# AB_shield.net
KiCad netlist of a schematic drawn in EAGLE
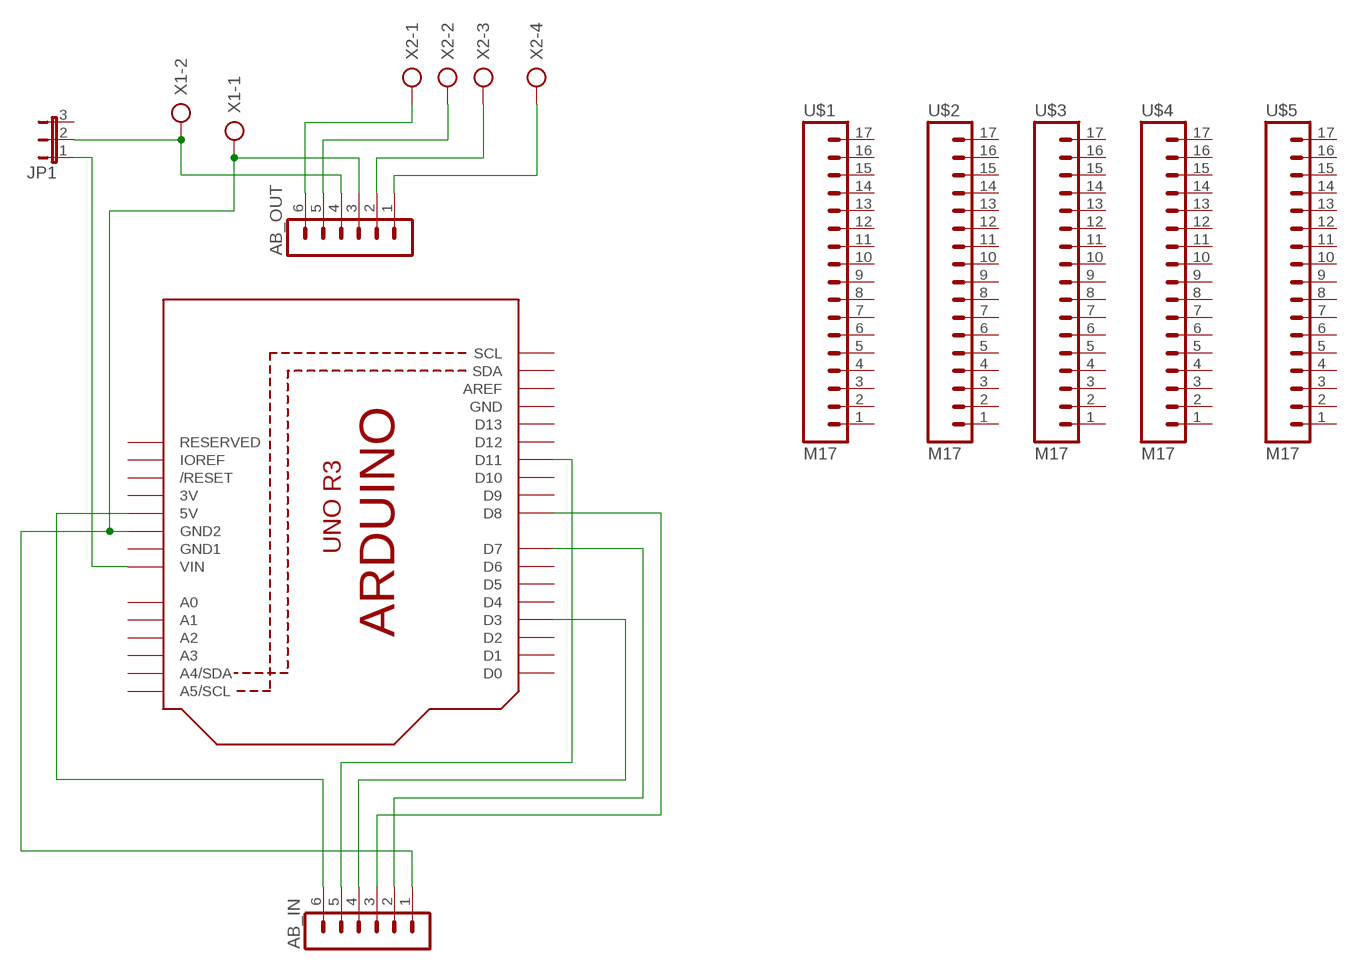
[diagram p0: schematic, sheet 1]

(export (version "E")
  (design (tool "Eeschema 10.0.6"))
  (components
    (comp (ref "AB_IN")
      (value "MA06-1")
      (footprint "eagle-import:MA06-1")
      (libsource (lib "eagle-import") (part "MA06-1"))
    )
    (comp (ref "AB_OUT")
      (value "MA06-1")
      (footprint "eagle-import:MA06-1")
      (libsource (lib "eagle-import") (part "MA06-1"))
    )
    (comp (ref "JP1")
      (value "JP2E")
      (footprint "eagle-import:JP2")
      (libsource (lib "eagle-import") (part "JP2E"))
    )
    (comp (ref "U$1")
      (value "M17")
      (footprint "eagle-import:1X17_PROTO")
      (libsource (lib "eagle-import") (part "M17"))
    )
    (comp (ref "U$2")
      (value "M17")
      (footprint "eagle-import:1X17_PROTO")
      (libsource (lib "eagle-import") (part "M17"))
    )
    (comp (ref "U$3")
      (value "M17")
      (footprint "eagle-import:1X17_PROTO")
      (libsource (lib "eagle-import") (part "M17"))
    )
    (comp (ref "U$4")
      (value "M17")
      (footprint "eagle-import:1X17_PROTO")
      (libsource (lib "eagle-import") (part "M17"))
    )
    (comp (ref "U$5")
      (value "M17")
      (footprint "eagle-import:1X17_PROTO")
      (libsource (lib "eagle-import") (part "M17"))
    )
    (comp (ref "U1")
      (value "ARDUINOR3-DIMENSION")
      (footprint "eagle-import:ARDUINOR3")
      (libsource (lib "eagle-import") (part "ARDUINOR3-DIMENSION"))
    )
    (comp (ref "X1")
      (value "AK500/2-H")
      (footprint "eagle-import:AK500_2-H")
      (libsource (lib "eagle-import") (part "AK500/2-H"))
    )
    (comp (ref "X2")
      (value "AK500/4")
      (footprint "eagle-import:AK500_4")
      (libsource (lib "eagle-import") (part "AK500/4"))
    )
  )
  (nets
    (net (code "1") (name "/3V") (class "Default")
      (node (ref "U1") (pin "3V") (pinfunction "3V_3V") (pintype "power_in"))
    )
    (net (code "2") (name "/GND") (class "Default")
      (node (ref "U1") (pin "GND") (pinfunction "GND_GND") (pintype "power_in"))
    )
    (net (code "3") (name "/GND1") (class "Default")
      (node (ref "U1") (pin "GND1") (pinfunction "GND1_GND1") (pintype "power_in"))
    )
    (net (code "4") (name "Net-(AB_IN-Pad2)") (class "Default")
      (node (ref "AB_IN") (pin "2") (pinfunction "2_2") (pintype "passive"))
      (node (ref "U1") (pin "D7") (pinfunction "D7_D7") (pintype "bidirectional"))
    )
    (net (code "5") (name "Net-(AB_IN-Pad3)") (class "Default")
      (node (ref "AB_IN") (pin "3") (pinfunction "3_3") (pintype "passive"))
      (node (ref "U1") (pin "D8") (pinfunction "D8_D8") (pintype "bidirectional"))
    )
    (net (code "6") (name "Net-(AB_IN-Pad4)") (class "Default")
      (node (ref "AB_IN") (pin "4") (pinfunction "4_4") (pintype "passive"))
      (node (ref "U1") (pin "D3") (pinfunction "D3_D3") (pintype "bidirectional"))
    )
    (net (code "7") (name "Net-(AB_IN-Pad5)") (class "Default")
      (node (ref "AB_IN") (pin "5") (pinfunction "5_5") (pintype "passive"))
      (node (ref "U1") (pin "D11") (pinfunction "D11_D11") (pintype "bidirectional"))
    )
    (net (code "8") (name "Net-(AB_IN-Pad6)") (class "Default")
      (node (ref "AB_IN") (pin "6") (pinfunction "6_6") (pintype "passive"))
      (node (ref "U1") (pin "5V") (pinfunction "5V_5V") (pintype "power_in"))
    )
    (net (code "9") (name "Net-(JP1-Pad1)") (class "Default")
      (node (ref "JP1") (pin "1") (pinfunction "1_1") (pintype "passive"))
      (node (ref "U1") (pin "VIN") (pinfunction "VIN_VIN") (pintype "power_in"))
    )
    (net (code "10") (name "Net-(X1A-KL)") (class "Default")
      (node (ref "AB_IN") (pin "1") (pinfunction "1_1") (pintype "passive"))
      (node (ref "AB_OUT") (pin "3") (pinfunction "3_3") (pintype "passive"))
      (node (ref "U1") (pin "GND2") (pinfunction "GND2_GND2") (pintype "power_in"))
      (node (ref "X1") (pin "1") (pinfunction "KL_1") (pintype "passive"))
    )
    (net (code "11") (name "Net-(X1B-KL)") (class "Default")
      (node (ref "AB_OUT") (pin "4") (pinfunction "4_4") (pintype "passive"))
      (node (ref "JP1") (pin "2") (pinfunction "2_2") (pintype "passive"))
      (node (ref "X1") (pin "2") (pinfunction "KL_2") (pintype "passive"))
    )
    (net (code "12") (name "Net-(X2A-KL)") (class "Default")
      (node (ref "AB_OUT") (pin "6") (pinfunction "6_6") (pintype "passive"))
      (node (ref "X2") (pin "1") (pinfunction "KL_1") (pintype "passive"))
    )
    (net (code "13") (name "Net-(X2B-KL)") (class "Default")
      (node (ref "AB_OUT") (pin "5") (pinfunction "5_5") (pintype "passive"))
      (node (ref "X2") (pin "2") (pinfunction "KL_2") (pintype "passive"))
    )
    (net (code "14") (name "Net-(X2C-KL)") (class "Default")
      (node (ref "AB_OUT") (pin "2") (pinfunction "2_2") (pintype "passive"))
      (node (ref "X2") (pin "3") (pinfunction "KL_3") (pintype "passive"))
    )
    (net (code "15") (name "Net-(X2D-KL)") (class "Default")
      (node (ref "AB_OUT") (pin "1") (pinfunction "1_1") (pintype "passive"))
      (node (ref "X2") (pin "4") (pinfunction "KL_4") (pintype "passive"))
    )
    (net (code "16") (name "unconnected-(JP1-Pad3)") (class "Default")
      (node (ref "JP1") (pin "3") (pinfunction "3_3") (pintype "passive"))
    )
    (net (code "17") (name "unconnected-(U$1-Pad1)") (class "Default")
      (node (ref "U$1") (pin "1") (pinfunction "1_1") (pintype "passive"))
    )
    (net (code "18") (name "unconnected-(U$1-Pad2)") (class "Default")
      (node (ref "U$1") (pin "2") (pinfunction "2_2") (pintype "passive"))
    )
    (net (code "19") (name "unconnected-(U$1-Pad3)") (class "Default")
      (node (ref "U$1") (pin "3") (pinfunction "3_3") (pintype "passive"))
    )
    (net (code "20") (name "unconnected-(U$1-Pad4)") (class "Default")
      (node (ref "U$1") (pin "4") (pinfunction "4_4") (pintype "passive"))
    )
    (net (code "21") (name "unconnected-(U$1-Pad5)") (class "Default")
      (node (ref "U$1") (pin "5") (pinfunction "5_5") (pintype "passive"))
    )
    (net (code "22") (name "unconnected-(U$1-Pad6)") (class "Default")
      (node (ref "U$1") (pin "6") (pinfunction "6_6") (pintype "passive"))
    )
    (net (code "23") (name "unconnected-(U$1-Pad7)") (class "Default")
      (node (ref "U$1") (pin "7") (pinfunction "7_7") (pintype "passive"))
    )
    (net (code "24") (name "unconnected-(U$1-Pad8)") (class "Default")
      (node (ref "U$1") (pin "8") (pinfunction "8_8") (pintype "passive"))
    )
    (net (code "25") (name "unconnected-(U$1-Pad9)") (class "Default")
      (node (ref "U$1") (pin "9") (pinfunction "9_9") (pintype "passive"))
    )
    (net (code "26") (name "unconnected-(U$1-Pad10)") (class "Default")
      (node (ref "U$1") (pin "10") (pinfunction "10_10") (pintype "passive"))
    )
    (net (code "27") (name "unconnected-(U$1-Pad11)") (class "Default")
      (node (ref "U$1") (pin "11") (pinfunction "11_11") (pintype "passive"))
    )
    (net (code "28") (name "unconnected-(U$1-Pad12)") (class "Default")
      (node (ref "U$1") (pin "12") (pinfunction "12_12") (pintype "passive"))
    )
    (net (code "29") (name "unconnected-(U$1-Pad13)") (class "Default")
      (node (ref "U$1") (pin "13") (pinfunction "13_13") (pintype "passive"))
    )
    (net (code "30") (name "unconnected-(U$1-Pad14)") (class "Default")
      (node (ref "U$1") (pin "14") (pinfunction "14_14") (pintype "passive"))
    )
    (net (code "31") (name "unconnected-(U$1-Pad15)") (class "Default")
      (node (ref "U$1") (pin "15") (pinfunction "15_15") (pintype "passive"))
    )
    (net (code "32") (name "unconnected-(U$1-Pad16)") (class "Default")
      (node (ref "U$1") (pin "16") (pinfunction "16_16") (pintype "passive"))
    )
    (net (code "33") (name "unconnected-(U$1-Pad17)") (class "Default")
      (node (ref "U$1") (pin "17") (pinfunction "17_17") (pintype "passive"))
    )
    (net (code "34") (name "unconnected-(U$2-Pad1)") (class "Default")
      (node (ref "U$2") (pin "1") (pinfunction "1_1") (pintype "passive"))
    )
    (net (code "35") (name "unconnected-(U$2-Pad2)") (class "Default")
      (node (ref "U$2") (pin "2") (pinfunction "2_2") (pintype "passive"))
    )
    (net (code "36") (name "unconnected-(U$2-Pad3)") (class "Default")
      (node (ref "U$2") (pin "3") (pinfunction "3_3") (pintype "passive"))
    )
    (net (code "37") (name "unconnected-(U$2-Pad4)") (class "Default")
      (node (ref "U$2") (pin "4") (pinfunction "4_4") (pintype "passive"))
    )
    (net (code "38") (name "unconnected-(U$2-Pad5)") (class "Default")
      (node (ref "U$2") (pin "5") (pinfunction "5_5") (pintype "passive"))
    )
    (net (code "39") (name "unconnected-(U$2-Pad6)") (class "Default")
      (node (ref "U$2") (pin "6") (pinfunction "6_6") (pintype "passive"))
    )
    (net (code "40") (name "unconnected-(U$2-Pad7)") (class "Default")
      (node (ref "U$2") (pin "7") (pinfunction "7_7") (pintype "passive"))
    )
    (net (code "41") (name "unconnected-(U$2-Pad8)") (class "Default")
      (node (ref "U$2") (pin "8") (pinfunction "8_8") (pintype "passive"))
    )
    (net (code "42") (name "unconnected-(U$2-Pad9)") (class "Default")
      (node (ref "U$2") (pin "9") (pinfunction "9_9") (pintype "passive"))
    )
    (net (code "43") (name "unconnected-(U$2-Pad10)") (class "Default")
      (node (ref "U$2") (pin "10") (pinfunction "10_10") (pintype "passive"))
    )
    (net (code "44") (name "unconnected-(U$2-Pad11)") (class "Default")
      (node (ref "U$2") (pin "11") (pinfunction "11_11") (pintype "passive"))
    )
    (net (code "45") (name "unconnected-(U$2-Pad12)") (class "Default")
      (node (ref "U$2") (pin "12") (pinfunction "12_12") (pintype "passive"))
    )
    (net (code "46") (name "unconnected-(U$2-Pad13)") (class "Default")
      (node (ref "U$2") (pin "13") (pinfunction "13_13") (pintype "passive"))
    )
    (net (code "47") (name "unconnected-(U$2-Pad14)") (class "Default")
      (node (ref "U$2") (pin "14") (pinfunction "14_14") (pintype "passive"))
    )
    (net (code "48") (name "unconnected-(U$2-Pad15)") (class "Default")
      (node (ref "U$2") (pin "15") (pinfunction "15_15") (pintype "passive"))
    )
    (net (code "49") (name "unconnected-(U$2-Pad16)") (class "Default")
      (node (ref "U$2") (pin "16") (pinfunction "16_16") (pintype "passive"))
    )
    (net (code "50") (name "unconnected-(U$2-Pad17)") (class "Default")
      (node (ref "U$2") (pin "17") (pinfunction "17_17") (pintype "passive"))
    )
    (net (code "51") (name "unconnected-(U$3-Pad1)") (class "Default")
      (node (ref "U$3") (pin "1") (pinfunction "1_1") (pintype "passive"))
    )
    (net (code "52") (name "unconnected-(U$3-Pad2)") (class "Default")
      (node (ref "U$3") (pin "2") (pinfunction "2_2") (pintype "passive"))
    )
    (net (code "53") (name "unconnected-(U$3-Pad3)") (class "Default")
      (node (ref "U$3") (pin "3") (pinfunction "3_3") (pintype "passive"))
    )
    (net (code "54") (name "unconnected-(U$3-Pad4)") (class "Default")
      (node (ref "U$3") (pin "4") (pinfunction "4_4") (pintype "passive"))
    )
    (net (code "55") (name "unconnected-(U$3-Pad5)") (class "Default")
      (node (ref "U$3") (pin "5") (pinfunction "5_5") (pintype "passive"))
    )
    (net (code "56") (name "unconnected-(U$3-Pad6)") (class "Default")
      (node (ref "U$3") (pin "6") (pinfunction "6_6") (pintype "passive"))
    )
    (net (code "57") (name "unconnected-(U$3-Pad7)") (class "Default")
      (node (ref "U$3") (pin "7") (pinfunction "7_7") (pintype "passive"))
    )
    (net (code "58") (name "unconnected-(U$3-Pad8)") (class "Default")
      (node (ref "U$3") (pin "8") (pinfunction "8_8") (pintype "passive"))
    )
    (net (code "59") (name "unconnected-(U$3-Pad9)") (class "Default")
      (node (ref "U$3") (pin "9") (pinfunction "9_9") (pintype "passive"))
    )
    (net (code "60") (name "unconnected-(U$3-Pad10)") (class "Default")
      (node (ref "U$3") (pin "10") (pinfunction "10_10") (pintype "passive"))
    )
    (net (code "61") (name "unconnected-(U$3-Pad11)") (class "Default")
      (node (ref "U$3") (pin "11") (pinfunction "11_11") (pintype "passive"))
    )
    (net (code "62") (name "unconnected-(U$3-Pad12)") (class "Default")
      (node (ref "U$3") (pin "12") (pinfunction "12_12") (pintype "passive"))
    )
    (net (code "63") (name "unconnected-(U$3-Pad13)") (class "Default")
      (node (ref "U$3") (pin "13") (pinfunction "13_13") (pintype "passive"))
    )
    (net (code "64") (name "unconnected-(U$3-Pad14)") (class "Default")
      (node (ref "U$3") (pin "14") (pinfunction "14_14") (pintype "passive"))
    )
    (net (code "65") (name "unconnected-(U$3-Pad15)") (class "Default")
      (node (ref "U$3") (pin "15") (pinfunction "15_15") (pintype "passive"))
    )
    (net (code "66") (name "unconnected-(U$3-Pad16)") (class "Default")
      (node (ref "U$3") (pin "16") (pinfunction "16_16") (pintype "passive"))
    )
    (net (code "67") (name "unconnected-(U$3-Pad17)") (class "Default")
      (node (ref "U$3") (pin "17") (pinfunction "17_17") (pintype "passive"))
    )
    (net (code "68") (name "unconnected-(U$4-Pad1)") (class "Default")
      (node (ref "U$4") (pin "1") (pinfunction "1_1") (pintype "passive"))
    )
    (net (code "69") (name "unconnected-(U$4-Pad2)") (class "Default")
      (node (ref "U$4") (pin "2") (pinfunction "2_2") (pintype "passive"))
    )
    (net (code "70") (name "unconnected-(U$4-Pad3)") (class "Default")
      (node (ref "U$4") (pin "3") (pinfunction "3_3") (pintype "passive"))
    )
    (net (code "71") (name "unconnected-(U$4-Pad4)") (class "Default")
      (node (ref "U$4") (pin "4") (pinfunction "4_4") (pintype "passive"))
    )
    (net (code "72") (name "unconnected-(U$4-Pad5)") (class "Default")
      (node (ref "U$4") (pin "5") (pinfunction "5_5") (pintype "passive"))
    )
    (net (code "73") (name "unconnected-(U$4-Pad6)") (class "Default")
      (node (ref "U$4") (pin "6") (pinfunction "6_6") (pintype "passive"))
    )
    (net (code "74") (name "unconnected-(U$4-Pad7)") (class "Default")
      (node (ref "U$4") (pin "7") (pinfunction "7_7") (pintype "passive"))
    )
    (net (code "75") (name "unconnected-(U$4-Pad8)") (class "Default")
      (node (ref "U$4") (pin "8") (pinfunction "8_8") (pintype "passive"))
    )
    (net (code "76") (name "unconnected-(U$4-Pad9)") (class "Default")
      (node (ref "U$4") (pin "9") (pinfunction "9_9") (pintype "passive"))
    )
    (net (code "77") (name "unconnected-(U$4-Pad10)") (class "Default")
      (node (ref "U$4") (pin "10") (pinfunction "10_10") (pintype "passive"))
    )
    (net (code "78") (name "unconnected-(U$4-Pad11)") (class "Default")
      (node (ref "U$4") (pin "11") (pinfunction "11_11") (pintype "passive"))
    )
    (net (code "79") (name "unconnected-(U$4-Pad12)") (class "Default")
      (node (ref "U$4") (pin "12") (pinfunction "12_12") (pintype "passive"))
    )
    (net (code "80") (name "unconnected-(U$4-Pad13)") (class "Default")
      (node (ref "U$4") (pin "13") (pinfunction "13_13") (pintype "passive"))
    )
    (net (code "81") (name "unconnected-(U$4-Pad14)") (class "Default")
      (node (ref "U$4") (pin "14") (pinfunction "14_14") (pintype "passive"))
    )
    (net (code "82") (name "unconnected-(U$4-Pad15)") (class "Default")
      (node (ref "U$4") (pin "15") (pinfunction "15_15") (pintype "passive"))
    )
    (net (code "83") (name "unconnected-(U$4-Pad16)") (class "Default")
      (node (ref "U$4") (pin "16") (pinfunction "16_16") (pintype "passive"))
    )
    (net (code "84") (name "unconnected-(U$4-Pad17)") (class "Default")
      (node (ref "U$4") (pin "17") (pinfunction "17_17") (pintype "passive"))
    )
    (net (code "85") (name "unconnected-(U$5-Pad1)") (class "Default")
      (node (ref "U$5") (pin "1") (pinfunction "1_1") (pintype "passive"))
    )
    (net (code "86") (name "unconnected-(U$5-Pad2)") (class "Default")
      (node (ref "U$5") (pin "2") (pinfunction "2_2") (pintype "passive"))
    )
    (net (code "87") (name "unconnected-(U$5-Pad3)") (class "Default")
      (node (ref "U$5") (pin "3") (pinfunction "3_3") (pintype "passive"))
    )
    (net (code "88") (name "unconnected-(U$5-Pad4)") (class "Default")
      (node (ref "U$5") (pin "4") (pinfunction "4_4") (pintype "passive"))
    )
    (net (code "89") (name "unconnected-(U$5-Pad5)") (class "Default")
      (node (ref "U$5") (pin "5") (pinfunction "5_5") (pintype "passive"))
    )
    (net (code "90") (name "unconnected-(U$5-Pad6)") (class "Default")
      (node (ref "U$5") (pin "6") (pinfunction "6_6") (pintype "passive"))
    )
    (net (code "91") (name "unconnected-(U$5-Pad7)") (class "Default")
      (node (ref "U$5") (pin "7") (pinfunction "7_7") (pintype "passive"))
    )
    (net (code "92") (name "unconnected-(U$5-Pad8)") (class "Default")
      (node (ref "U$5") (pin "8") (pinfunction "8_8") (pintype "passive"))
    )
    (net (code "93") (name "unconnected-(U$5-Pad9)") (class "Default")
      (node (ref "U$5") (pin "9") (pinfunction "9_9") (pintype "passive"))
    )
    (net (code "94") (name "unconnected-(U$5-Pad10)") (class "Default")
      (node (ref "U$5") (pin "10") (pinfunction "10_10") (pintype "passive"))
    )
    (net (code "95") (name "unconnected-(U$5-Pad11)") (class "Default")
      (node (ref "U$5") (pin "11") (pinfunction "11_11") (pintype "passive"))
    )
    (net (code "96") (name "unconnected-(U$5-Pad12)") (class "Default")
      (node (ref "U$5") (pin "12") (pinfunction "12_12") (pintype "passive"))
    )
    (net (code "97") (name "unconnected-(U$5-Pad13)") (class "Default")
      (node (ref "U$5") (pin "13") (pinfunction "13_13") (pintype "passive"))
    )
    (net (code "98") (name "unconnected-(U$5-Pad14)") (class "Default")
      (node (ref "U$5") (pin "14") (pinfunction "14_14") (pintype "passive"))
    )
    (net (code "99") (name "unconnected-(U$5-Pad15)") (class "Default")
      (node (ref "U$5") (pin "15") (pinfunction "15_15") (pintype "passive"))
    )
    (net (code "100") (name "unconnected-(U$5-Pad16)") (class "Default")
      (node (ref "U$5") (pin "16") (pinfunction "16_16") (pintype "passive"))
    )
    (net (code "101") (name "unconnected-(U$5-Pad17)") (class "Default")
      (node (ref "U$5") (pin "17") (pinfunction "17_17") (pintype "passive"))
    )
    (net (code "102") (name "unconnected-(U1-A4{slash}SDA-PadA4)") (class "Default")
      (node (ref "U1") (pin "A4") (pinfunction "A4/SDA_A4") (pintype "bidirectional"))
    )
    (net (code "103") (name "unconnected-(U1-A5{slash}SCL-PadA5)") (class "Default")
      (node (ref "U1") (pin "A5") (pinfunction "A5/SCL_A5") (pintype "bidirectional"))
    )
    (net (code "104") (name "unconnected-(U1-PadA0)") (class "Default")
      (node (ref "U1") (pin "A0") (pinfunction "A0_A0") (pintype "bidirectional"))
    )
    (net (code "105") (name "unconnected-(U1-PadA1)") (class "Default")
      (node (ref "U1") (pin "A1") (pinfunction "A1_A1") (pintype "bidirectional"))
    )
    (net (code "106") (name "unconnected-(U1-PadA2)") (class "Default")
      (node (ref "U1") (pin "A2") (pinfunction "A2_A2") (pintype "bidirectional"))
    )
    (net (code "107") (name "unconnected-(U1-PadA3)") (class "Default")
      (node (ref "U1") (pin "A3") (pinfunction "A3_A3") (pintype "bidirectional"))
    )
    (net (code "108") (name "unconnected-(U1-PadAREF)") (class "Default")
      (node (ref "U1") (pin "AREF") (pinfunction "AREF_AREF") (pintype "bidirectional"))
    )
    (net (code "109") (name "unconnected-(U1-PadD0)") (class "Default")
      (node (ref "U1") (pin "D0") (pinfunction "D0_D0") (pintype "bidirectional"))
    )
    (net (code "110") (name "unconnected-(U1-PadD1)") (class "Default")
      (node (ref "U1") (pin "D1") (pinfunction "D1_D1") (pintype "bidirectional"))
    )
    (net (code "111") (name "unconnected-(U1-PadD2)") (class "Default")
      (node (ref "U1") (pin "D2") (pinfunction "D2_D2") (pintype "bidirectional"))
    )
    (net (code "112") (name "unconnected-(U1-PadD4)") (class "Default")
      (node (ref "U1") (pin "D4") (pinfunction "D4_D4") (pintype "bidirectional"))
    )
    (net (code "113") (name "unconnected-(U1-PadD5)") (class "Default")
      (node (ref "U1") (pin "D5") (pinfunction "D5_D5") (pintype "bidirectional"))
    )
    (net (code "114") (name "unconnected-(U1-PadD6)") (class "Default")
      (node (ref "U1") (pin "D6") (pinfunction "D6_D6") (pintype "bidirectional"))
    )
    (net (code "115") (name "unconnected-(U1-PadD9)") (class "Default")
      (node (ref "U1") (pin "D9") (pinfunction "D9_D9") (pintype "bidirectional"))
    )
    (net (code "116") (name "unconnected-(U1-PadD10)") (class "Default")
      (node (ref "U1") (pin "D10") (pinfunction "D10_D10") (pintype "bidirectional"))
    )
    (net (code "117") (name "unconnected-(U1-PadD12)") (class "Default")
      (node (ref "U1") (pin "D12") (pinfunction "D12_D12") (pintype "bidirectional"))
    )
    (net (code "118") (name "unconnected-(U1-PadD13)") (class "Default")
      (node (ref "U1") (pin "D13") (pinfunction "D13_D13") (pintype "bidirectional"))
    )
    (net (code "119") (name "unconnected-(U1-PadIOREF)") (class "Default")
      (node (ref "U1") (pin "IOREF") (pinfunction "IOREF_IOREF") (pintype "output"))
    )
    (net (code "120") (name "unconnected-(U1-PadRESERVED)") (class "Default")
      (node (ref "U1") (pin "RESERVED") (pinfunction "RESERVED_RESERVED") (pintype "no_connect"))
    )
    (net (code "121") (name "unconnected-(U1-PadSCL)") (class "Default")
      (node (ref "U1") (pin "SCL") (pinfunction "SCL_SCL") (pintype "bidirectional"))
    )
    (net (code "122") (name "unconnected-(U1-PadSDA)") (class "Default")
      (node (ref "U1") (pin "SDA") (pinfunction "SDA_SDA") (pintype "bidirectional"))
    )
    (net (code "123") (name "unconnected-(U1-{slash}RESET-PadRESET)") (class "Default")
      (node (ref "U1") (pin "RESET") (pinfunction "/RESET_RESET") (pintype "bidirectional"))
    )
  )
)
